# FE1_1S.net
KiCad netlist of a schematic drawn in Altium Designer
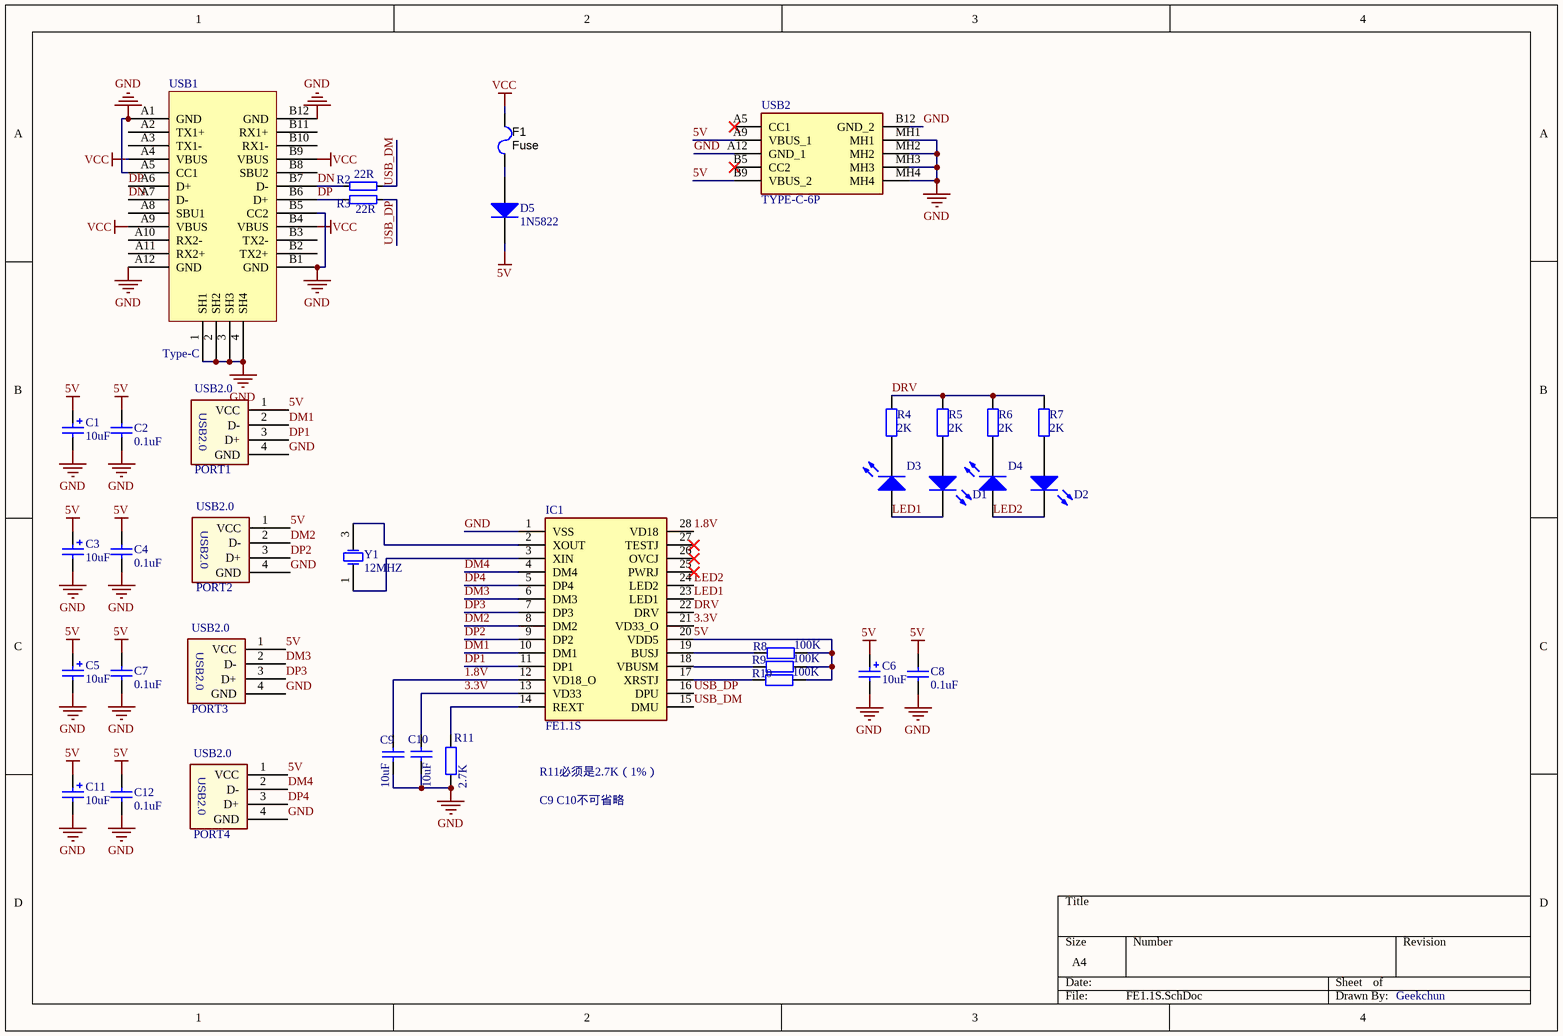
[diagram p0: FE1.1S.SchDoc]

(export (version "E")
  (design (tool "Eeschema 10.0.6"))
  (components
    (comp (ref "C1")
      (value "10uF")
      (footprint "CASE-A_3216")
      (description "钽电容")
      (libsource (lib "嘉立创") (part "3216 10uF (106) 10% 16V"))
    )
    (comp (ref "C2")
      (value "0.1uF")
      (footprint "C 0603_L")
      (description "贴片电容")
      (libsource (lib "嘉立创") (part "0603 2.2uF (225) 10% 16V"))
    )
    (comp (ref "C3")
      (value "10uF")
      (footprint "CASE-A_3216")
      (description "钽电容")
      (libsource (lib "嘉立创") (part "3216 10uF (106) 10% 16V"))
    )
    (comp (ref "C4")
      (value "0.1uF")
      (footprint "C 0603_L")
      (description "贴片电容")
      (libsource (lib "嘉立创") (part "0603 2.2uF (225) 10% 16V"))
    )
    (comp (ref "C5")
      (value "10uF")
      (footprint "CASE-A_3216")
      (description "钽电容")
      (libsource (lib "嘉立创") (part "3216 10uF (106) 10% 16V"))
    )
    (comp (ref "C6")
      (value "10uF")
      (footprint "CASE-A_3216")
      (description "钽电容")
      (libsource (lib "嘉立创") (part "3216 10uF (106) 10% 16V"))
    )
    (comp (ref "C7")
      (value "0.1uF")
      (footprint "C 0603_L")
      (description "贴片电容")
      (libsource (lib "嘉立创") (part "0603 2.2uF (225) 10% 16V"))
    )
    (comp (ref "C8")
      (value "0.1uF")
      (footprint "C 0603_L")
      (description "贴片电容")
      (libsource (lib "嘉立创") (part "0603 2.2uF (225) 10% 16V"))
    )
    (comp (ref "C9")
      (value "10uF")
      (footprint "C 0603_L")
      (description "贴片电容")
      (libsource (lib "嘉立创") (part "0603 1.2nF (122) 10% 50V"))
    )
    (comp (ref "C10")
      (value "10uF")
      (footprint "C 0603_L")
      (description "贴片电容")
      (libsource (lib "嘉立创") (part "0603 1.2nF (122) 10% 50V"))
    )
    (comp (ref "C11")
      (value "10uF")
      (footprint "CASE-A_3216")
      (description "钽电容")
      (libsource (lib "嘉立创") (part "3216 10uF (106) 10% 16V"))
    )
    (comp (ref "C12")
      (value "0.1uF")
      (footprint "C 0603_L")
      (description "贴片电容")
      (libsource (lib "嘉立创") (part "0603 2.2uF (225) 10% 16V"))
    )
    (comp (ref "D1")
      (value "蓝灯 0603")
      (footprint "0603_LED_S1")
      (description "发光二极管")
      (libsource (lib "嘉立创") (part "0603 蓝灯"))
    )
    (comp (ref "D2")
      (value "蓝灯 0603")
      (footprint "0603_LED_S1")
      (description "发光二极管")
      (libsource (lib "嘉立创") (part "0603 蓝灯"))
    )
    (comp (ref "D3")
      (value "蓝灯 0603")
      (footprint "0603_LED_S1")
      (description "发光二极管")
      (libsource (lib "嘉立创") (part "0603 蓝灯"))
    )
    (comp (ref "D4")
      (value "蓝灯 0603")
      (footprint "0603_LED_S1")
      (description "发光二极管")
      (libsource (lib "嘉立创") (part "0603 蓝灯"))
    )
    (comp (ref "D5")
      (value "1N5822")
      (footprint "SMA")
      (description "3 Amp General Purpose Rectifier")
      (fields (field (name "PUBLISHER") "Altium Limited"))
      (libsource (lib "Miscellaneous Devices") (part "Diode 1N5400"))
    )
    (comp (ref "F1")
      (value "Fuse")
      (footprint "FU 1206")
      (fields
        (field (name "PARTNUMBER") "NANOSMDC020F-2")
        (field (name "MANUFACTURER") "TE Connectivity")
        (field (name "PUBLISHER") "Texas Instruments")
        (field (name "SYMBOLCREATOR") "a0412235")
      )
      (libsource (lib "TUSB8041_USB_3.0_Hub") (part "Fuse"))
    )
    (comp (ref "IC1")
      (value "FE1.1S")
      (footprint "SamacSys:SOP64P600X175-28N")
      (description "Integrated Circuit")
      (libsource (lib "*") (part "FE1.1S"))
    )
    (comp (ref "PORT1")
      (value "USB2.0")
      (footprint "USB-A/S_A")
      (libsource (lib "SamacSys") (part "USB2.0_1"))
    )
    (comp (ref "PORT2") (value "USB2.0") (footprint "USB-A/S_A") (libsource (lib "") (part "USB2.0_1_1")))
    (comp (ref "PORT3") (value "USB2.0") (footprint "USB-A/S_A") (libsource (lib "") (part "USB2.0_1_3")))
    (comp (ref "PORT4") (value "USB2.0") (footprint "USB-A/S_A") (libsource (lib "") (part "USB2.0_1_2")))
    (comp (ref "R2") (value "22R") (footprint "R 0603_L") (libsource (lib "电阻") (part "RES")))
    (comp (ref "R3") (value "22R") (footprint "R 0603_L") (libsource (lib "电阻") (part "RES")))
    (comp (ref "R4")
      (value "2K")
      (footprint "R 0603_L")
      (description "贴片电阻")
      (libsource (lib "") (part "0603 1.1KΩ (1101) 1%_1"))
    )
    (comp (ref "R5")
      (value "2K")
      (footprint "R 0603_L")
      (description "贴片电阻")
      (libsource (lib "") (part "0603 1.1KΩ (1101) 1%_1"))
    )
    (comp (ref "R6")
      (value "2K")
      (footprint "R 0603_L")
      (description "贴片电阻")
      (libsource (lib "") (part "0603 1.1KΩ (1101) 1%_1"))
    )
    (comp (ref "R7")
      (value "2K")
      (footprint "R 0603_L")
      (description "贴片电阻")
      (libsource (lib "") (part "0603 1.1KΩ (1101) 1%_1"))
    )
    (comp (ref "R8")
      (value "100K")
      (footprint "R 0603_L")
      (description "贴片电阻")
      (libsource (lib "嘉立创") (part "0603 1.1KΩ (1101) 1%"))
    )
    (comp (ref "R9")
      (value "100K")
      (footprint "R 0603_L")
      (description "贴片电阻")
      (libsource (lib "嘉立创") (part "0603 1.1KΩ (1101) 1%"))
    )
    (comp (ref "R10")
      (value "100K")
      (footprint "R 0603_L")
      (description "贴片电阻")
      (libsource (lib "嘉立创") (part "0603 1.1KΩ (1101) 1%"))
    )
    (comp (ref "R11")
      (value "2.7K")
      (footprint "R 0603_L")
      (description "贴片电阻")
      (libsource (lib "") (part "0603 1.1KΩ (1101) 1%_1"))
    )
    (comp (ref "USB1") (value "Type-C") (footprint "USB_TYPE_C_16P") (libsource (lib "元件") (part "Type-C")))
    (comp (ref "USB2")
      (value "TYPE-C-6P")
      (footprint "USB TYPEC6P")
      (description "Connector")
      (fields (field (name "MANUFACTURER_PART_NUMBER") "TYPE-C-31-M-17"))
      (libsource (lib "SamacSys") (part "TYPE-C-31-M-17"))
    )
    (comp (ref "Y1")
      (value "12MHZ")
      (footprint "OSC 3225-4P")
      (description "贴片晶振")
      (libsource (lib "嘉立创") (part "SMD-3225_4P  12MHZ 20PF 10PPM"))
    )
  )
  (nets
    (net (code "1") (name "/1.8V") (class "Default")
      (node (ref "C9") (pin "2") (pinfunction "2_2") (pintype "passive"))
      (node (ref "IC1") (pin "12") (pinfunction "VD18_O_12") (pintype "passive"))
      (node (ref "IC1") (pin "28") (pinfunction "VD18_28") (pintype "passive"))
    )
    (net (code "2") (name "/3.3V") (class "Default")
      (node (ref "C10") (pin "2") (pinfunction "2_2") (pintype "passive"))
      (node (ref "IC1") (pin "13") (pinfunction "VD33_13") (pintype "passive"))
      (node (ref "IC1") (pin "21") (pinfunction "VD33_O_21") (pintype "passive"))
    )
    (net (code "3") (name "/DM1") (class "Default")
      (node (ref "IC1") (pin "10") (pinfunction "DM1_10") (pintype "passive"))
      (node (ref "PORT1") (pin "2") (pinfunction "D-_2") (pintype "passive"))
    )
    (net (code "4") (name "/DM2") (class "Default")
      (node (ref "IC1") (pin "8") (pinfunction "DM2_8") (pintype "passive"))
      (node (ref "PORT2") (pin "2") (pinfunction "D-_2") (pintype "passive"))
    )
    (net (code "5") (name "/DM3") (class "Default")
      (node (ref "IC1") (pin "6") (pinfunction "DM3_6") (pintype "passive"))
      (node (ref "PORT3") (pin "2") (pinfunction "D-_2") (pintype "passive"))
    )
    (net (code "6") (name "/DM4") (class "Default")
      (node (ref "IC1") (pin "4") (pinfunction "DM4_4") (pintype "passive"))
      (node (ref "PORT4") (pin "2") (pinfunction "D-_2") (pintype "passive"))
    )
    (net (code "7") (name "/DN") (class "Default")
      (node (ref "R2") (pin "1") (pinfunction "1_1") (pintype "passive"))
      (node (ref "USB1") (pin "A7") (pinfunction "D-_A7") (pintype "passive"))
      (node (ref "USB1") (pin "B7") (pinfunction "D-_B7") (pintype "passive"))
    )
    (net (code "8") (name "/DP") (class "Default")
      (node (ref "R3") (pin "1") (pinfunction "1_1") (pintype "passive"))
      (node (ref "USB1") (pin "A6") (pinfunction "D+_A6") (pintype "passive"))
      (node (ref "USB1") (pin "B6") (pinfunction "D+_B6") (pintype "passive"))
    )
    (net (code "9") (name "/DP1") (class "Default")
      (node (ref "IC1") (pin "11") (pinfunction "DP1_11") (pintype "passive"))
      (node (ref "PORT1") (pin "3") (pinfunction "D+_3") (pintype "passive"))
    )
    (net (code "10") (name "/DP2") (class "Default")
      (node (ref "IC1") (pin "9") (pinfunction "DP2_9") (pintype "passive"))
      (node (ref "PORT2") (pin "3") (pinfunction "D+_3") (pintype "passive"))
    )
    (net (code "11") (name "/DP3") (class "Default")
      (node (ref "IC1") (pin "7") (pinfunction "DP3_7") (pintype "passive"))
      (node (ref "PORT3") (pin "3") (pinfunction "D+_3") (pintype "passive"))
    )
    (net (code "12") (name "/DP4") (class "Default")
      (node (ref "IC1") (pin "5") (pinfunction "DP4_5") (pintype "passive"))
      (node (ref "PORT4") (pin "3") (pinfunction "D+_3") (pintype "passive"))
    )
    (net (code "13") (name "/DRV") (class "Default")
      (node (ref "IC1") (pin "22") (pinfunction "DRV_22") (pintype "passive"))
      (node (ref "R4") (pin "2") (pinfunction "2_2") (pintype "passive"))
      (node (ref "R5") (pin "2") (pinfunction "2_2") (pintype "passive"))
      (node (ref "R6") (pin "2") (pinfunction "2_2") (pintype "passive"))
      (node (ref "R7") (pin "2") (pinfunction "2_2") (pintype "passive"))
    )
    (net (code "14") (name "/LED1") (class "Default")
      (node (ref "D1") (pin "K") (pinfunction "K_K") (pintype "passive"))
      (node (ref "D3") (pin "A") (pinfunction "A_A") (pintype "passive"))
      (node (ref "IC1") (pin "23") (pinfunction "LED1_23") (pintype "passive"))
    )
    (net (code "15") (name "/LED2") (class "Default")
      (node (ref "D2") (pin "K") (pinfunction "K_K") (pintype "passive"))
      (node (ref "D4") (pin "A") (pinfunction "A_A") (pintype "passive"))
      (node (ref "IC1") (pin "24") (pinfunction "LED2_24") (pintype "passive"))
    )
    (net (code "16") (name "/USB_DM") (class "Default")
      (node (ref "IC1") (pin "15") (pinfunction "DMU_15") (pintype "passive"))
      (node (ref "R2") (pin "2") (pinfunction "2_2") (pintype "passive"))
    )
    (net (code "17") (name "/USB_DP") (class "Default")
      (node (ref "IC1") (pin "16") (pinfunction "DPU_16") (pintype "passive"))
      (node (ref "R3") (pin "2") (pinfunction "2_2") (pintype "passive"))
    )
    (net (code "18") (name "5V") (class "Default")
      (node (ref "C1") (pin "1") (pinfunction "1_1") (pintype "passive"))
      (node (ref "C11") (pin "1") (pinfunction "1_1") (pintype "passive"))
      (node (ref "C12") (pin "2") (pinfunction "2_2") (pintype "passive"))
      (node (ref "C2") (pin "2") (pinfunction "2_2") (pintype "passive"))
      (node (ref "C3") (pin "1") (pinfunction "1_1") (pintype "passive"))
      (node (ref "C4") (pin "2") (pinfunction "2_2") (pintype "passive"))
      (node (ref "C5") (pin "1") (pinfunction "1_1") (pintype "passive"))
      (node (ref "C6") (pin "1") (pinfunction "1_1") (pintype "passive"))
      (node (ref "C7") (pin "2") (pinfunction "2_2") (pintype "passive"))
      (node (ref "C8") (pin "2") (pinfunction "2_2") (pintype "passive"))
      (node (ref "D5") (pin "2") (pinfunction "K_2") (pintype "passive"))
      (node (ref "IC1") (pin "20") (pinfunction "VDD5_20") (pintype "passive"))
      (node (ref "PORT1") (pin "1") (pinfunction "VCC_1") (pintype "power_in"))
      (node (ref "PORT2") (pin "1") (pinfunction "VCC_1") (pintype "power_in"))
      (node (ref "PORT3") (pin "1") (pinfunction "VCC_1") (pintype "power_in"))
      (node (ref "PORT4") (pin "1") (pinfunction "VCC_1") (pintype "power_in"))
      (node (ref "R10") (pin "1") (pinfunction "1_1") (pintype "passive"))
      (node (ref "R8") (pin "1") (pinfunction "1_1") (pintype "passive"))
      (node (ref "R9") (pin "1") (pinfunction "1_1") (pintype "passive"))
      (node (ref "USB2") (pin "A9") (pinfunction "VBUS_1_A9") (pintype "passive"))
      (node (ref "USB2") (pin "B9") (pinfunction "VBUS_2_B9") (pintype "passive"))
    )
    (net (code "19") (name "GND") (class "Default")
      (node (ref "C1") (pin "2") (pinfunction "2_2") (pintype "passive"))
      (node (ref "C10") (pin "1") (pinfunction "1_1") (pintype "passive"))
      (node (ref "C11") (pin "2") (pinfunction "2_2") (pintype "passive"))
      (node (ref "C12") (pin "1") (pinfunction "1_1") (pintype "passive"))
      (node (ref "C2") (pin "1") (pinfunction "1_1") (pintype "passive"))
      (node (ref "C3") (pin "2") (pinfunction "2_2") (pintype "passive"))
      (node (ref "C4") (pin "1") (pinfunction "1_1") (pintype "passive"))
      (node (ref "C5") (pin "2") (pinfunction "2_2") (pintype "passive"))
      (node (ref "C6") (pin "2") (pinfunction "2_2") (pintype "passive"))
      (node (ref "C7") (pin "1") (pinfunction "1_1") (pintype "passive"))
      (node (ref "C8") (pin "1") (pinfunction "1_1") (pintype "passive"))
      (node (ref "C9") (pin "1") (pinfunction "1_1") (pintype "passive"))
      (node (ref "IC1") (pin "1") (pinfunction "VSS_1") (pintype "passive"))
      (node (ref "PORT1") (pin "4") (pinfunction "GND_4") (pintype "power_in"))
      (node (ref "PORT2") (pin "4") (pinfunction "GND_4") (pintype "power_in"))
      (node (ref "PORT3") (pin "4") (pinfunction "GND_4") (pintype "power_in"))
      (node (ref "PORT4") (pin "4") (pinfunction "GND_4") (pintype "power_in"))
      (node (ref "R11") (pin "1") (pinfunction "1_1") (pintype "passive"))
      (node (ref "USB1") (pin "1") (pinfunction "SH1_1") (pintype "passive"))
      (node (ref "USB1") (pin "2") (pinfunction "SH2_2") (pintype "passive"))
      (node (ref "USB1") (pin "3") (pinfunction "SH3_3") (pintype "passive"))
      (node (ref "USB1") (pin "4") (pinfunction "SH4_4") (pintype "passive"))
      (node (ref "USB1") (pin "A1") (pinfunction "GND_A1") (pintype "passive"))
      (node (ref "USB1") (pin "A12") (pinfunction "GND_A12") (pintype "passive"))
      (node (ref "USB1") (pin "A5") (pinfunction "CC1_A5") (pintype "passive"))
      (node (ref "USB1") (pin "B1") (pinfunction "GND_B1") (pintype "passive"))
      (node (ref "USB1") (pin "B12") (pinfunction "GND_B12") (pintype "passive"))
      (node (ref "USB1") (pin "B5") (pinfunction "CC2_B5") (pintype "passive"))
      (node (ref "USB2") (pin "A12") (pinfunction "GND_1_A12") (pintype "passive"))
      (node (ref "USB2") (pin "B12") (pinfunction "GND_2_B12") (pintype "passive"))
      (node (ref "USB2") (pin "MH1") (pinfunction "MH1_MH1") (pintype "passive"))
      (node (ref "USB2") (pin "MH2") (pinfunction "MH2_MH2") (pintype "passive"))
      (node (ref "USB2") (pin "MH3") (pinfunction "MH3_MH3") (pintype "passive"))
      (node (ref "USB2") (pin "MH4") (pinfunction "MH4_MH4") (pintype "passive"))
    )
    (net (code "20") (name "Net-(D1-PadA)") (class "Default")
      (node (ref "D1") (pin "A") (pinfunction "A_A") (pintype "passive"))
      (node (ref "R5") (pin "1") (pinfunction "1_1") (pintype "passive"))
    )
    (net (code "21") (name "Net-(D2-PadA)") (class "Default")
      (node (ref "D2") (pin "A") (pinfunction "A_A") (pintype "passive"))
      (node (ref "R7") (pin "1") (pinfunction "1_1") (pintype "passive"))
    )
    (net (code "22") (name "Net-(D3-PadK)") (class "Default")
      (node (ref "D3") (pin "K") (pinfunction "K_K") (pintype "passive"))
      (node (ref "R4") (pin "1") (pinfunction "1_1") (pintype "passive"))
    )
    (net (code "23") (name "Net-(D4-PadK)") (class "Default")
      (node (ref "D4") (pin "K") (pinfunction "K_K") (pintype "passive"))
      (node (ref "R6") (pin "1") (pinfunction "1_1") (pintype "passive"))
    )
    (net (code "24") (name "Net-(D5-A)") (class "Default")
      (node (ref "D5") (pin "1") (pinfunction "A_1") (pintype "passive"))
      (node (ref "F1") (pin "2") (pinfunction "2_2") (pintype "passive"))
    )
    (net (code "25") (name "Net-(IC1-BUSJ)") (class "Default")
      (node (ref "IC1") (pin "19") (pinfunction "BUSJ_19") (pintype "passive"))
      (node (ref "R8") (pin "2") (pinfunction "2_2") (pintype "passive"))
    )
    (net (code "26") (name "Net-(IC1-REXT)") (class "Default")
      (node (ref "IC1") (pin "14") (pinfunction "REXT_14") (pintype "passive"))
      (node (ref "R11") (pin "2") (pinfunction "2_2") (pintype "passive"))
    )
    (net (code "27") (name "Net-(IC1-VBUSM)") (class "Default")
      (node (ref "IC1") (pin "18") (pinfunction "VBUSM_18") (pintype "passive"))
      (node (ref "R9") (pin "2") (pinfunction "2_2") (pintype "passive"))
    )
    (net (code "28") (name "Net-(IC1-XIN)") (class "Default")
      (node (ref "IC1") (pin "3") (pinfunction "XIN_3") (pintype "passive"))
      (node (ref "Y1") (pin "1") (pinfunction "OSC1_1") (pintype "passive"))
    )
    (net (code "29") (name "Net-(IC1-XOUT)") (class "Default")
      (node (ref "IC1") (pin "2") (pinfunction "XOUT_2") (pintype "passive"))
      (node (ref "Y1") (pin "3") (pinfunction "OSC2_3") (pintype "passive"))
    )
    (net (code "30") (name "Net-(IC1-XRSTJ)") (class "Default")
      (node (ref "IC1") (pin "17") (pinfunction "XRSTJ_17") (pintype "passive"))
      (node (ref "R10") (pin "2") (pinfunction "2_2") (pintype "passive"))
    )
    (net (code "31") (name "VCC") (class "Default")
      (node (ref "F1") (pin "1") (pinfunction "1_1") (pintype "passive"))
      (node (ref "USB1") (pin "A4") (pinfunction "VBUS_A4") (pintype "passive"))
      (node (ref "USB1") (pin "A9") (pinfunction "VBUS_A9") (pintype "passive"))
      (node (ref "USB1") (pin "B4") (pinfunction "VBUS_B4") (pintype "passive"))
      (node (ref "USB1") (pin "B9") (pinfunction "VBUS_B9") (pintype "passive"))
    )
    (net (code "32") (name "unconnected-(IC1-OVCJ-Pad26)") (class "Default")
      (node (ref "IC1") (pin "26") (pinfunction "OVCJ_26") (pintype "passive+no_connect"))
    )
    (net (code "33") (name "unconnected-(IC1-PWRJ-Pad25)") (class "Default")
      (node (ref "IC1") (pin "25") (pinfunction "PWRJ_25") (pintype "passive+no_connect"))
    )
    (net (code "34") (name "unconnected-(IC1-TESTJ-Pad27)") (class "Default")
      (node (ref "IC1") (pin "27") (pinfunction "TESTJ_27") (pintype "passive+no_connect"))
    )
    (net (code "35") (name "unconnected-(USB1-RX1+-PadB11)") (class "Default")
      (node (ref "USB1") (pin "B11") (pinfunction "RX1+_B11") (pintype "passive"))
    )
    (net (code "36") (name "unconnected-(USB1-RX1--PadB10)") (class "Default")
      (node (ref "USB1") (pin "B10") (pinfunction "RX1-_B10") (pintype "passive"))
    )
    (net (code "37") (name "unconnected-(USB1-RX2+-PadA11)") (class "Default")
      (node (ref "USB1") (pin "A11") (pinfunction "RX2+_A11") (pintype "passive"))
    )
    (net (code "38") (name "unconnected-(USB1-RX2--PadA10)") (class "Default")
      (node (ref "USB1") (pin "A10") (pinfunction "RX2-_A10") (pintype "passive"))
    )
    (net (code "39") (name "unconnected-(USB1-SBU1-PadA8)") (class "Default")
      (node (ref "USB1") (pin "A8") (pinfunction "SBU1_A8") (pintype "passive"))
    )
    (net (code "40") (name "unconnected-(USB1-SBU2-PadB8)") (class "Default")
      (node (ref "USB1") (pin "B8") (pinfunction "SBU2_B8") (pintype "passive"))
    )
    (net (code "41") (name "unconnected-(USB1-TX1+-PadA2)") (class "Default")
      (node (ref "USB1") (pin "A2") (pinfunction "TX1+_A2") (pintype "passive"))
    )
    (net (code "42") (name "unconnected-(USB1-TX1--PadA3)") (class "Default")
      (node (ref "USB1") (pin "A3") (pinfunction "TX1-_A3") (pintype "passive"))
    )
    (net (code "43") (name "unconnected-(USB1-TX2+-PadB2)") (class "Default")
      (node (ref "USB1") (pin "B2") (pinfunction "TX2+_B2") (pintype "passive"))
    )
    (net (code "44") (name "unconnected-(USB1-TX2--PadB3)") (class "Default")
      (node (ref "USB1") (pin "B3") (pinfunction "TX2-_B3") (pintype "passive"))
    )
    (net (code "45") (name "unconnected-(USB2-CC1-PadA5)") (class "Default")
      (node (ref "USB2") (pin "A5") (pinfunction "CC1_A5") (pintype "passive+no_connect"))
    )
    (net (code "46") (name "unconnected-(USB2-CC2-PadB5)") (class "Default")
      (node (ref "USB2") (pin "B5") (pinfunction "CC2_B5") (pintype "passive+no_connect"))
    )
  )
)
